# main.net
KiCad netlist of a schematic drawn in EAGLE
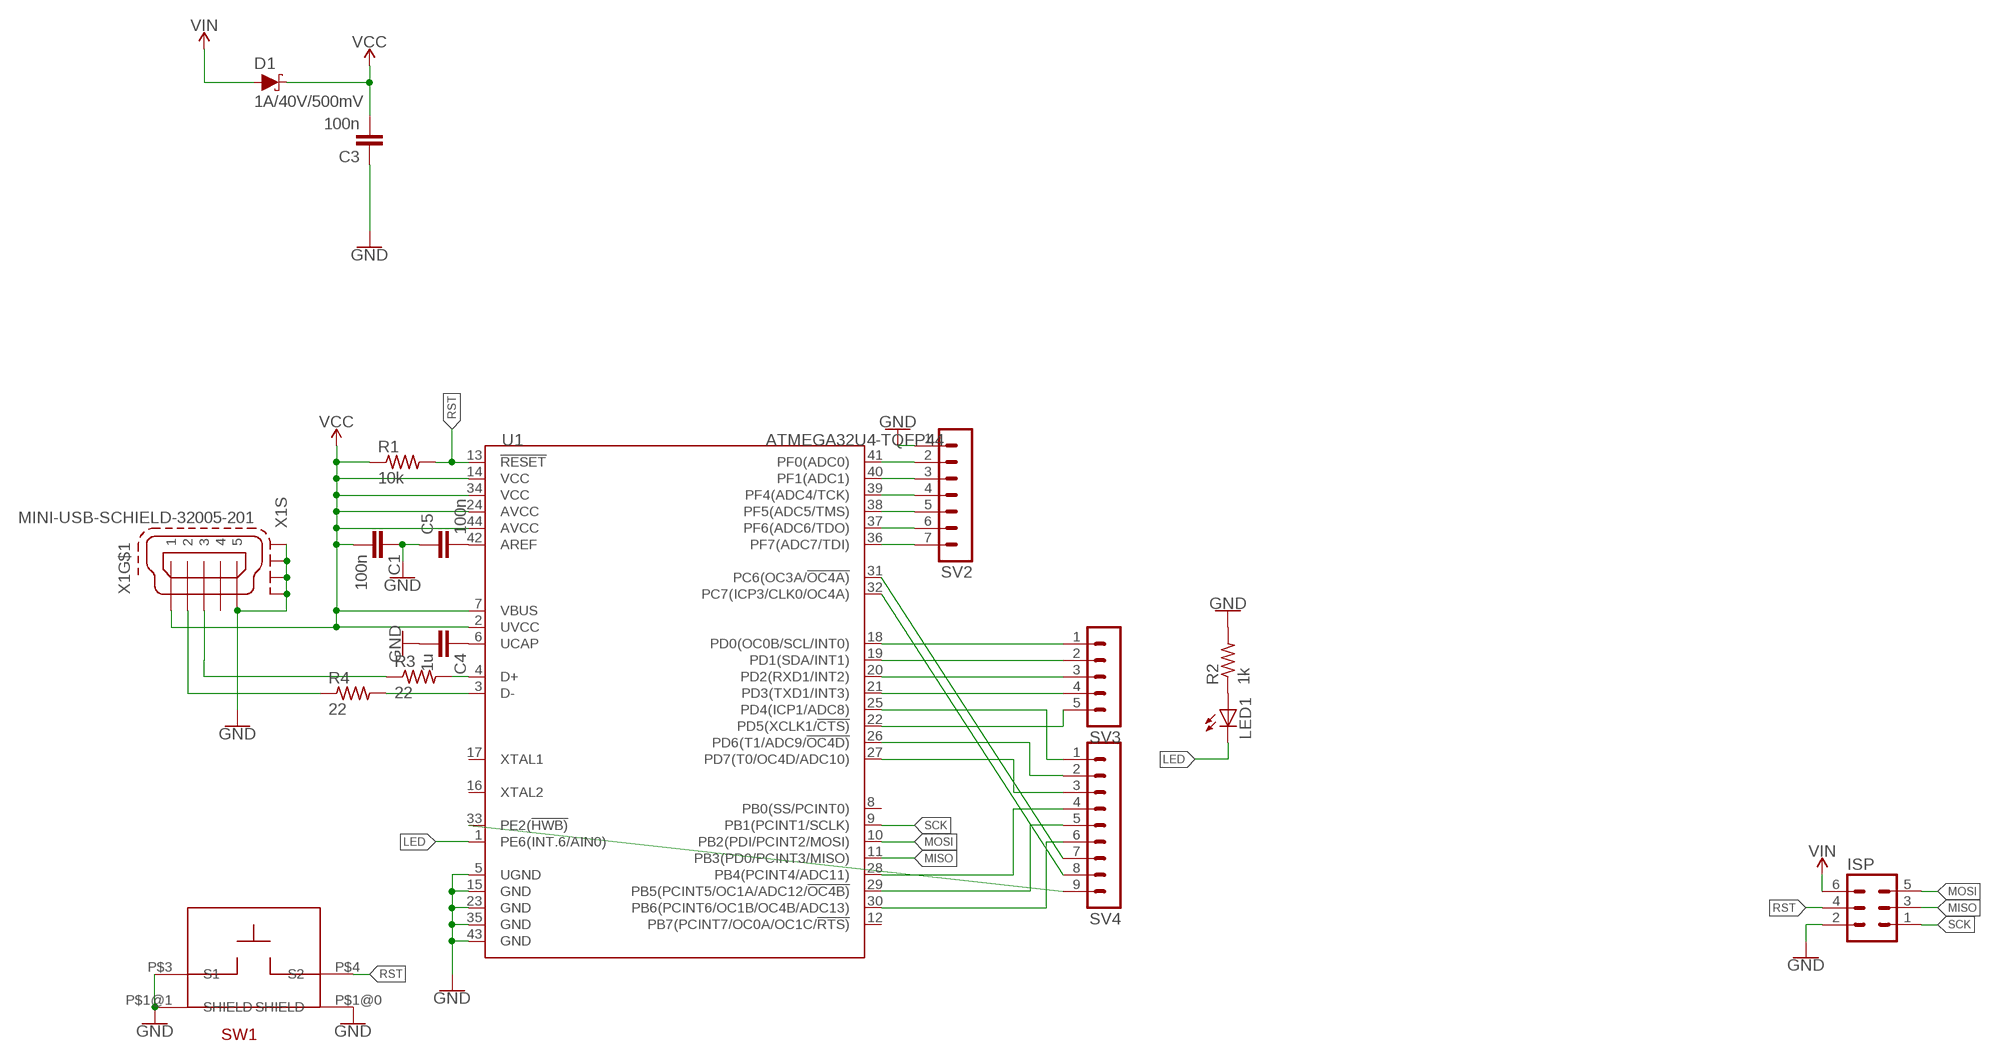
[diagram p0: schematic, sheet 1]

(export (version "E")
  (design (tool "Eeschema 10.0.6"))
  (components
    (comp (ref "C1")
      (value "100n")
      (footprint "eagle-import:C0402")
      (libsource (lib "eagle-import") (part "C-EUC0402"))
    )
    (comp (ref "C3")
      (value "100n")
      (footprint "eagle-import:C0603")
      (libsource (lib "eagle-import") (part "C-EUC0603"))
    )
    (comp (ref "C4")
      (value "1u")
      (footprint "eagle-import:C0603")
      (libsource (lib "eagle-import") (part "C-EUC0603"))
    )
    (comp (ref "C5")
      (value "100n")
      (footprint "eagle-import:C0603")
      (libsource (lib "eagle-import") (part "C-EUC0603"))
    )
    (comp (ref "D1")
      (value "1A/40V/500mV")
      (footprint "eagle-import:SMA-DIODE")
      (libsource (lib "eagle-import") (part "DIODE-SCHOTTKY-SS14"))
    )
    (comp (ref "ISP")
      (value "MA03-2")
      (footprint "eagle-import:MA03-2")
      (libsource (lib "eagle-import") (part "MA03-2"))
    )
    (comp (ref "LED1")
      (value "LEDCHIP-LED0603")
      (footprint "eagle-import:CHIP-LED0603")
      (libsource (lib "eagle-import") (part "LEDCHIP-LED0603"))
    )
    (comp (ref "R1")
      (value "10k")
      (footprint "eagle-import:R0603")
      (libsource (lib "eagle-import") (part "R-US_R0603"))
    )
    (comp (ref "R2")
      (value "1k")
      (footprint "eagle-import:R0603")
      (libsource (lib "eagle-import") (part "R-US_R0603"))
    )
    (comp (ref "R3")
      (value "22")
      (footprint "eagle-import:R0603")
      (libsource (lib "eagle-import") (part "R-US_R0603"))
    )
    (comp (ref "R4")
      (value "22")
      (footprint "eagle-import:R0603")
      (libsource (lib "eagle-import") (part "R-US_R0603"))
    )
    (comp (ref "SV2")
      (value "MA07-1")
      (footprint "eagle-import:MA07-1")
      (libsource (lib "eagle-import") (part "MA07-1"))
    )
    (comp (ref "SV3")
      (value "MA05-1")
      (footprint "eagle-import:MA05-1")
      (libsource (lib "eagle-import") (part "MA05-1"))
    )
    (comp (ref "SV4")
      (value "MA09-1")
      (footprint "eagle-import:MA09-1")
      (libsource (lib "eagle-import") (part "MA09-1"))
    )
    (comp (ref "SW1")
      (value "TL3330")
      (footprint "eagle-import:TL3330")
      (libsource (lib "eagle-import") (part "TL3330"))
    )
    (comp (ref "U1")
      (value "ATMEGA32U4-TQFP44")
      (footprint "eagle-import:TQFP44-0.8-9.6X9.6MM")
      (fields (field (name "MPN") "ATMEGA32U4"))
      (libsource (lib "eagle-import") (part "MCU-ATMEGA32U4-AU(TQFP44)"))
    )
    (comp (ref "X1")
      (value "MINI-USB-SCHIELD-32005-201")
      (footprint "eagle-import:32005-201")
      (libsource (lib "eagle-import") (part "MINI-USB-SCHIELD-32005-201"))
    )
  )
  (nets
    (net (code "1") (name "GND") (class "Default")
      (node (ref "C1") (pin "1") (pinfunction "1_1") (pintype "passive"))
      (node (ref "C3") (pin "1") (pinfunction "1_1") (pintype "passive"))
      (node (ref "C4") (pin "2") (pinfunction "2_2") (pintype "passive"))
      (node (ref "C5") (pin "1") (pinfunction "1_1") (pintype "passive"))
      (node (ref "ISP") (pin "2") (pinfunction "2_2") (pintype "passive"))
      (node (ref "R2") (pin "2") (pinfunction "2_2") (pintype "passive"))
      (node (ref "SV2") (pin "1") (pinfunction "1_1") (pintype "passive"))
      (node (ref "SW1") (pin "P$1@0") (pinfunction "SHIELD_P$1@0") (pintype "bidirectional"))
      (node (ref "SW1") (pin "P$1@1") (pinfunction "SHIELD_P$1@1") (pintype "bidirectional"))
      (node (ref "SW1") (pin "P$3") (pinfunction "S1_P$3") (pintype "bidirectional"))
      (node (ref "U1") (pin "15") (pinfunction "GND_15") (pintype "bidirectional"))
      (node (ref "U1") (pin "23") (pinfunction "GND_23") (pintype "bidirectional"))
      (node (ref "U1") (pin "35") (pinfunction "GND_35") (pintype "bidirectional"))
      (node (ref "U1") (pin "43") (pinfunction "GND_43") (pintype "bidirectional"))
      (node (ref "U1") (pin "5") (pinfunction "UGND_5") (pintype "bidirectional"))
      (node (ref "X1") (pin "5") (pinfunction "5_5") (pintype "passive"))
      (node (ref "X1") (pin "M1") (pinfunction "S1_M1") (pintype "passive"))
      (node (ref "X1") (pin "M2") (pinfunction "S2_M2") (pintype "passive"))
      (node (ref "X1") (pin "M3") (pinfunction "S3_M3") (pintype "passive"))
      (node (ref "X1") (pin "M4") (pinfunction "S4_M4") (pintype "passive"))
    )
    (net (code "2") (name "LED") (class "Default")
      (node (ref "LED1") (pin "C") (pinfunction "C_C") (pintype "passive"))
      (node (ref "U1") (pin "1") (pinfunction "PE6(INT.6/AIN0)_1") (pintype "bidirectional"))
    )
    (net (code "3") (name "MISO") (class "Default")
      (node (ref "ISP") (pin "3") (pinfunction "3_3") (pintype "passive"))
      (node (ref "U1") (pin "11") (pinfunction "PB3(PD0/PCINT3/MISO)_11") (pintype "bidirectional"))
    )
    (net (code "4") (name "MOSI") (class "Default")
      (node (ref "ISP") (pin "5") (pinfunction "5_5") (pintype "passive"))
      (node (ref "U1") (pin "10") (pinfunction "PB2(PDI/PCINT2/MOSI)_10") (pintype "bidirectional"))
    )
    (net (code "5") (name "Net-(LED1-PadA)") (class "Default")
      (node (ref "LED1") (pin "A") (pinfunction "A_A") (pintype "passive"))
      (node (ref "R2") (pin "1") (pinfunction "1_1") (pintype "passive"))
    )
    (net (code "6") (name "Net-(R3-Pad1)") (class "Default")
      (node (ref "R3") (pin "1") (pinfunction "1_1") (pintype "passive"))
      (node (ref "X1") (pin "3") (pinfunction "3_3") (pintype "passive"))
    )
    (net (code "7") (name "Net-(R4-Pad1)") (class "Default")
      (node (ref "R4") (pin "1") (pinfunction "1_1") (pintype "passive"))
      (node (ref "X1") (pin "2") (pinfunction "2_2") (pintype "passive"))
    )
    (net (code "8") (name "Net-(U1-AREF)") (class "Default")
      (node (ref "C5") (pin "2") (pinfunction "2_2") (pintype "passive"))
      (node (ref "U1") (pin "42") (pinfunction "AREF_42") (pintype "bidirectional"))
    )
    (net (code "9") (name "Net-(U1-D+)") (class "Default")
      (node (ref "R3") (pin "2") (pinfunction "2_2") (pintype "passive"))
      (node (ref "U1") (pin "4") (pinfunction "D+_4") (pintype "bidirectional"))
    )
    (net (code "10") (name "Net-(U1-D-)") (class "Default")
      (node (ref "R4") (pin "2") (pinfunction "2_2") (pintype "passive"))
      (node (ref "U1") (pin "3") (pinfunction "D-_3") (pintype "bidirectional"))
    )
    (net (code "11") (name "Net-(U1-PB4(PCINT4{slash}ADC11))") (class "Default")
      (node (ref "SV4") (pin "4") (pinfunction "4_4") (pintype "passive"))
      (node (ref "U1") (pin "28") (pinfunction "PB4(PCINT4/ADC11)_28") (pintype "bidirectional"))
    )
    (net (code "12") (name "Net-(U1-PB5(PCINT5{slash}OC1A{slash}ADC12{slash}~{OC4B}))") (class "Default")
      (node (ref "SV4") (pin "5") (pinfunction "5_5") (pintype "passive"))
      (node (ref "U1") (pin "29") (pinfunction "PB5(PCINT5/OC1A/ADC12/~{OC4B})_29") (pintype "bidirectional"))
    )
    (net (code "13") (name "Net-(U1-PB6(PCINT6{slash}OC1B{slash}OC4B{slash}ADC13))") (class "Default")
      (node (ref "SV4") (pin "6") (pinfunction "6_6") (pintype "passive"))
      (node (ref "U1") (pin "30") (pinfunction "PB6(PCINT6/OC1B/OC4B/ADC13)_30") (pintype "bidirectional"))
    )
    (net (code "14") (name "Net-(U1-PC6(OC3A{slash}~{OC4A}))") (class "Default")
      (node (ref "SV4") (pin "7") (pinfunction "7_7") (pintype "passive"))
      (node (ref "U1") (pin "31") (pinfunction "PC6(OC3A/~{OC4A})_31") (pintype "bidirectional"))
    )
    (net (code "15") (name "Net-(U1-PC7(ICP3{slash}CLK0{slash}OC4A))") (class "Default")
      (node (ref "SV4") (pin "8") (pinfunction "8_8") (pintype "passive"))
      (node (ref "U1") (pin "32") (pinfunction "PC7(ICP3/CLK0/OC4A)_32") (pintype "bidirectional"))
    )
    (net (code "16") (name "Net-(U1-PD0(OC0B{slash}SCL{slash}INT0))") (class "Default")
      (node (ref "SV3") (pin "1") (pinfunction "1_1") (pintype "passive"))
      (node (ref "U1") (pin "18") (pinfunction "PD0(OC0B/SCL/INT0)_18") (pintype "bidirectional"))
    )
    (net (code "17") (name "Net-(U1-PD1(SDA{slash}INT1))") (class "Default")
      (node (ref "SV3") (pin "2") (pinfunction "2_2") (pintype "passive"))
      (node (ref "U1") (pin "19") (pinfunction "PD1(SDA/INT1)_19") (pintype "bidirectional"))
    )
    (net (code "18") (name "Net-(U1-PD2(RXD1{slash}INT2))") (class "Default")
      (node (ref "SV3") (pin "3") (pinfunction "3_3") (pintype "passive"))
      (node (ref "U1") (pin "20") (pinfunction "PD2(RXD1/INT2)_20") (pintype "bidirectional"))
    )
    (net (code "19") (name "Net-(U1-PD3(TXD1{slash}INT3))") (class "Default")
      (node (ref "SV3") (pin "4") (pinfunction "4_4") (pintype "passive"))
      (node (ref "U1") (pin "21") (pinfunction "PD3(TXD1/INT3)_21") (pintype "bidirectional"))
    )
    (net (code "20") (name "Net-(U1-PD4(ICP1{slash}ADC8))") (class "Default")
      (node (ref "SV4") (pin "1") (pinfunction "1_1") (pintype "passive"))
      (node (ref "U1") (pin "25") (pinfunction "PD4(ICP1/ADC8)_25") (pintype "bidirectional"))
    )
    (net (code "21") (name "Net-(U1-PD5(XCLK1{slash}~{CTS}))") (class "Default")
      (node (ref "SV3") (pin "5") (pinfunction "5_5") (pintype "passive"))
      (node (ref "U1") (pin "22") (pinfunction "PD5(XCLK1/~{CTS})_22") (pintype "bidirectional"))
    )
    (net (code "22") (name "Net-(U1-PD6(T1{slash}ADC9{slash}~{OC4D}))") (class "Default")
      (node (ref "SV4") (pin "2") (pinfunction "2_2") (pintype "passive"))
      (node (ref "U1") (pin "26") (pinfunction "PD6(T1/ADC9/~{OC4D})_26") (pintype "bidirectional"))
    )
    (net (code "23") (name "Net-(U1-PD7(T0{slash}OC4D{slash}ADC10))") (class "Default")
      (node (ref "SV4") (pin "3") (pinfunction "3_3") (pintype "passive"))
      (node (ref "U1") (pin "27") (pinfunction "PD7(T0/OC4D/ADC10)_27") (pintype "bidirectional"))
    )
    (net (code "24") (name "Net-(U1-PE2(~{HWB}))") (class "Default")
      (node (ref "SV4") (pin "9") (pinfunction "9_9") (pintype "passive"))
      (node (ref "U1") (pin "33") (pinfunction "PE2(~{HWB})_33") (pintype "bidirectional"))
    )
    (net (code "25") (name "Net-(U1-PF0(ADC0))") (class "Default")
      (node (ref "SV2") (pin "2") (pinfunction "2_2") (pintype "passive"))
      (node (ref "U1") (pin "41") (pinfunction "PF0(ADC0)_41") (pintype "bidirectional"))
    )
    (net (code "26") (name "Net-(U1-PF1(ADC1))") (class "Default")
      (node (ref "SV2") (pin "3") (pinfunction "3_3") (pintype "passive"))
      (node (ref "U1") (pin "40") (pinfunction "PF1(ADC1)_40") (pintype "bidirectional"))
    )
    (net (code "27") (name "Net-(U1-PF4(ADC4{slash}TCK))") (class "Default")
      (node (ref "SV2") (pin "4") (pinfunction "4_4") (pintype "passive"))
      (node (ref "U1") (pin "39") (pinfunction "PF4(ADC4/TCK)_39") (pintype "bidirectional"))
    )
    (net (code "28") (name "Net-(U1-PF5(ADC5{slash}TMS))") (class "Default")
      (node (ref "SV2") (pin "5") (pinfunction "5_5") (pintype "passive"))
      (node (ref "U1") (pin "38") (pinfunction "PF5(ADC5/TMS)_38") (pintype "bidirectional"))
    )
    (net (code "29") (name "Net-(U1-PF6(ADC6{slash}TDO))") (class "Default")
      (node (ref "SV2") (pin "6") (pinfunction "6_6") (pintype "passive"))
      (node (ref "U1") (pin "37") (pinfunction "PF6(ADC6/TDO)_37") (pintype "bidirectional"))
    )
    (net (code "30") (name "Net-(U1-PF7(ADC7{slash}TDI))") (class "Default")
      (node (ref "SV2") (pin "7") (pinfunction "7_7") (pintype "passive"))
      (node (ref "U1") (pin "36") (pinfunction "PF7(ADC7/TDI)_36") (pintype "bidirectional"))
    )
    (net (code "31") (name "Net-(U1-UCAP)") (class "Default")
      (node (ref "C4") (pin "1") (pinfunction "1_1") (pintype "passive"))
      (node (ref "U1") (pin "6") (pinfunction "UCAP_6") (pintype "bidirectional"))
    )
    (net (code "32") (name "RST") (class "Default")
      (node (ref "ISP") (pin "4") (pinfunction "4_4") (pintype "passive"))
      (node (ref "R1") (pin "2") (pinfunction "2_2") (pintype "passive"))
      (node (ref "SW1") (pin "P$4") (pinfunction "S2_P$4") (pintype "bidirectional"))
      (node (ref "U1") (pin "13") (pinfunction "~{RESET}_13") (pintype "bidirectional"))
    )
    (net (code "33") (name "SCK") (class "Default")
      (node (ref "ISP") (pin "1") (pinfunction "1_1") (pintype "passive"))
      (node (ref "U1") (pin "9") (pinfunction "PB1(PCINT1/SCLK)_9") (pintype "bidirectional"))
    )
    (net (code "34") (name "VCC") (class "Default")
      (node (ref "C1") (pin "2") (pinfunction "2_2") (pintype "passive"))
      (node (ref "C3") (pin "2") (pinfunction "2_2") (pintype "passive"))
      (node (ref "D1") (pin "C") (pinfunction "C_C") (pintype "passive"))
      (node (ref "R1") (pin "1") (pinfunction "1_1") (pintype "passive"))
      (node (ref "U1") (pin "14") (pinfunction "VCC_14") (pintype "bidirectional"))
      (node (ref "U1") (pin "2") (pinfunction "UVCC_2") (pintype "bidirectional"))
      (node (ref "U1") (pin "24") (pinfunction "AVCC_24") (pintype "bidirectional"))
      (node (ref "U1") (pin "34") (pinfunction "VCC_34") (pintype "bidirectional"))
      (node (ref "U1") (pin "44") (pinfunction "AVCC_44") (pintype "bidirectional"))
      (node (ref "U1") (pin "7") (pinfunction "VBUS_7") (pintype "bidirectional"))
      (node (ref "X1") (pin "1") (pinfunction "1_1") (pintype "passive"))
    )
    (net (code "35") (name "VIN") (class "Default")
      (node (ref "D1") (pin "A") (pinfunction "A_A") (pintype "passive"))
      (node (ref "ISP") (pin "6") (pinfunction "6_6") (pintype "passive"))
    )
    (net (code "36") (name "unconnected-(U1-PB0(SS{slash}PCINT0)-Pad8)") (class "Default")
      (node (ref "U1") (pin "8") (pinfunction "PB0(SS/PCINT0)_8") (pintype "bidirectional"))
    )
    (net (code "37") (name "unconnected-(U1-PB7(PCINT7{slash}OC0A{slash}OC1C{slash}~{RTS})-Pad12)") (class "Default")
      (node (ref "U1") (pin "12") (pinfunction "PB7(PCINT7/OC0A/OC1C/~{RTS})_12") (pintype "bidirectional"))
    )
    (net (code "38") (name "unconnected-(U1-XTAL1-Pad17)") (class "Default")
      (node (ref "U1") (pin "17") (pinfunction "XTAL1_17") (pintype "bidirectional"))
    )
    (net (code "39") (name "unconnected-(U1-XTAL2-Pad16)") (class "Default")
      (node (ref "U1") (pin "16") (pinfunction "XTAL2_16") (pintype "bidirectional"))
    )
    (net (code "40") (name "unconnected-(X1-Pad4)") (class "Default")
      (node (ref "X1") (pin "4") (pinfunction "4_4") (pintype "passive"))
    )
  )
)
